# Matrix.net
KiCad netlist of a schematic drawn in Altium Designer
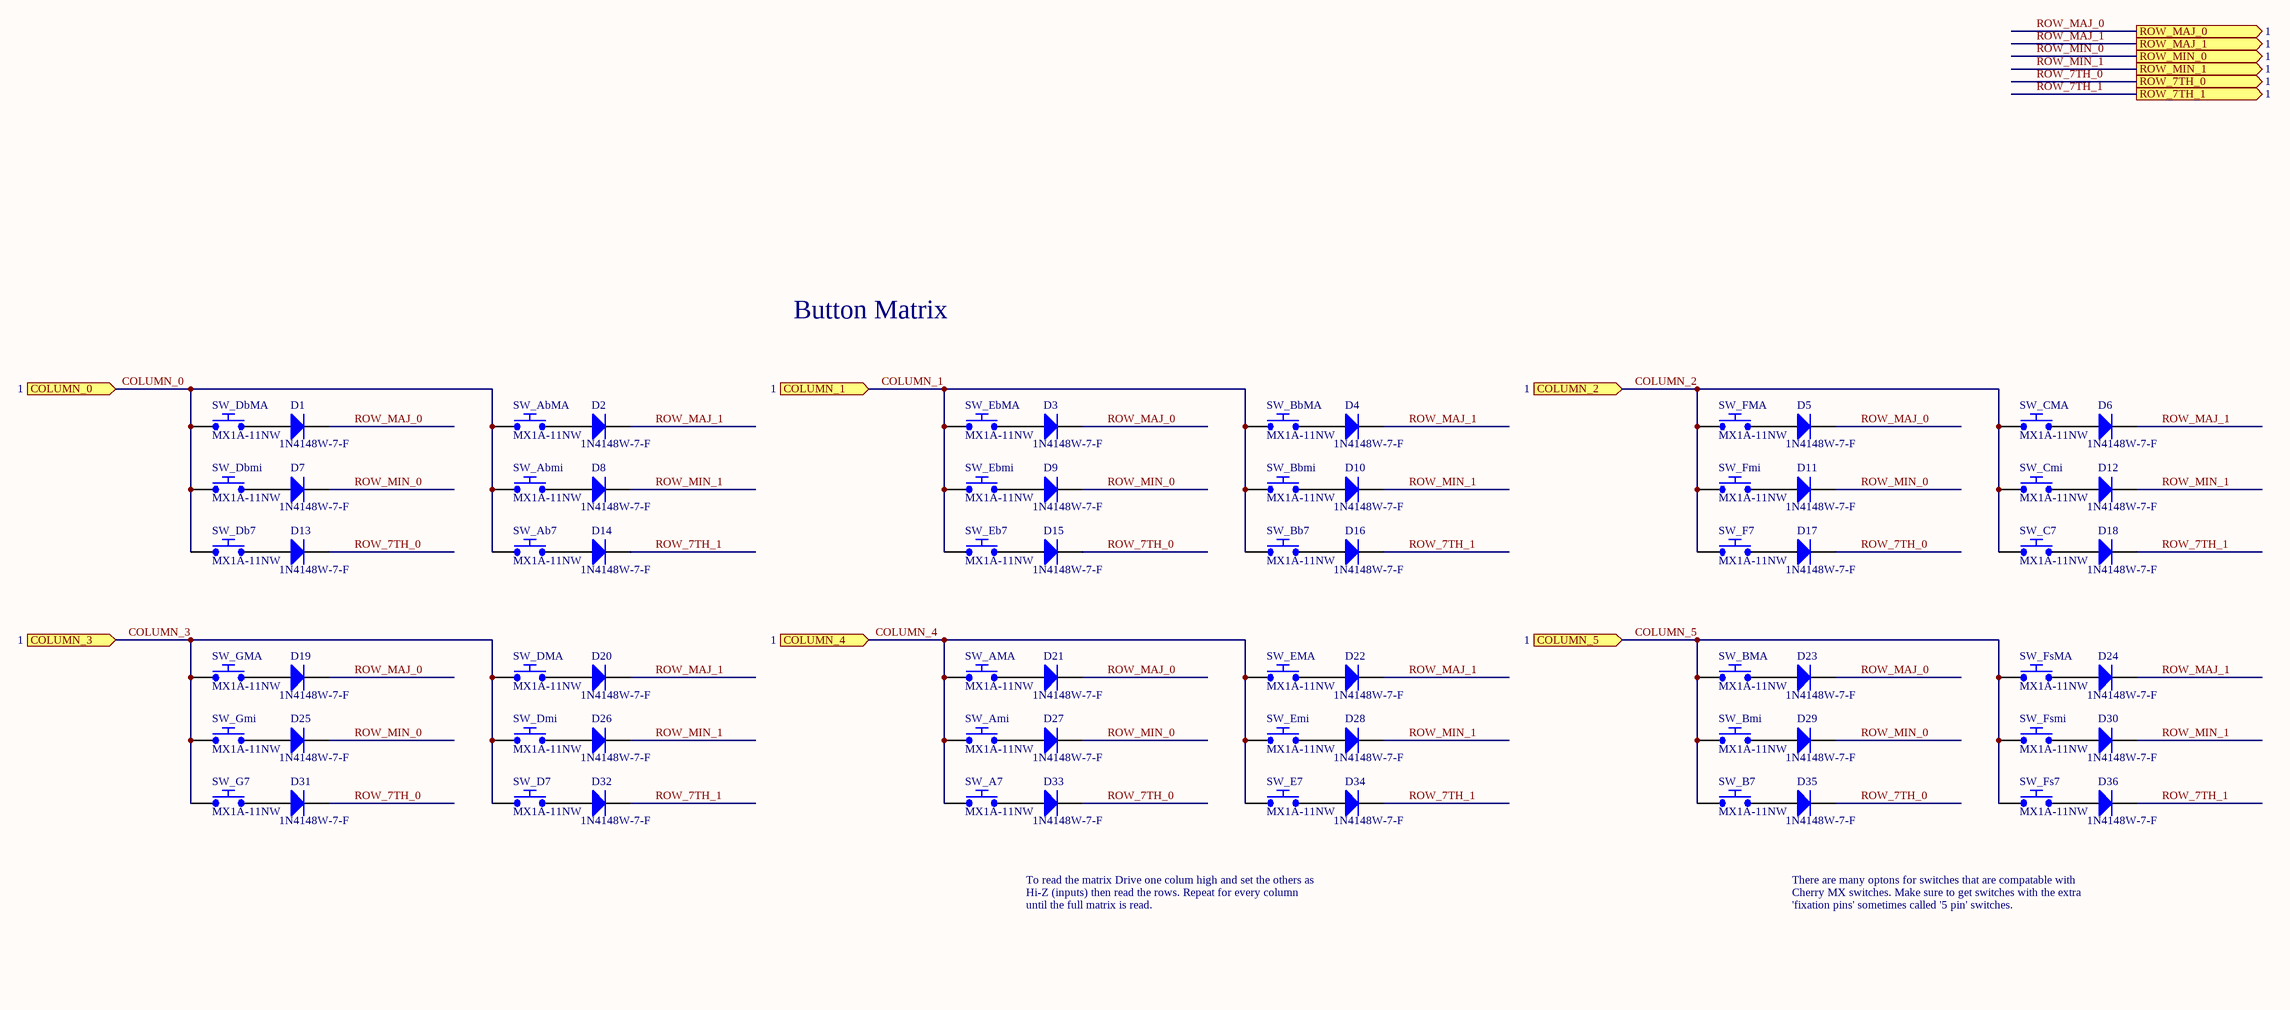
[diagram p0: Matrix.SchDoc]

(export (version "E")
  (design (tool "Eeschema 10.0.6"))
  (components
    (comp (ref "D1")
      (value "1N4148W-7-F")
      (footprint "SOD-123")
      (description "DIODE SWITCH 100V 0.15A SOD123")
      (fields (field (name "MANUFACTURER") "Diodes Incorporated"))
      (libsource (lib "Semiconductor") (part "DIODE"))
    )
    (comp (ref "D2")
      (value "1N4148W-7-F")
      (footprint "SOD-123")
      (description "DIODE SWITCH 100V 0.15A SOD123")
      (fields (field (name "MANUFACTURER") "Diodes Incorporated"))
      (libsource (lib "Semiconductor") (part "DIODE"))
    )
    (comp (ref "D3")
      (value "1N4148W-7-F")
      (footprint "SOD-123")
      (description "DIODE SWITCH 100V 0.15A SOD123")
      (fields (field (name "MANUFACTURER") "Diodes Incorporated"))
      (libsource (lib "Semiconductor") (part "DIODE"))
    )
    (comp (ref "D4")
      (value "1N4148W-7-F")
      (footprint "SOD-123")
      (description "DIODE SWITCH 100V 0.15A SOD123")
      (fields (field (name "MANUFACTURER") "Diodes Incorporated"))
      (libsource (lib "Semiconductor") (part "DIODE"))
    )
    (comp (ref "D5")
      (value "1N4148W-7-F")
      (footprint "SOD-123")
      (description "DIODE SWITCH 100V 0.15A SOD123")
      (fields (field (name "MANUFACTURER") "Diodes Incorporated"))
      (libsource (lib "Semiconductor") (part "DIODE"))
    )
    (comp (ref "D6")
      (value "1N4148W-7-F")
      (footprint "SOD-123")
      (description "DIODE SWITCH 100V 0.15A SOD123")
      (fields (field (name "MANUFACTURER") "Diodes Incorporated"))
      (libsource (lib "Semiconductor") (part "DIODE"))
    )
    (comp (ref "D7")
      (value "1N4148W-7-F")
      (footprint "SOD-123")
      (description "DIODE SWITCH 100V 0.15A SOD123")
      (fields (field (name "MANUFACTURER") "Diodes Incorporated"))
      (libsource (lib "Semiconductor") (part "DIODE"))
    )
    (comp (ref "D8")
      (value "1N4148W-7-F")
      (footprint "SOD-123")
      (description "DIODE SWITCH 100V 0.15A SOD123")
      (fields (field (name "MANUFACTURER") "Diodes Incorporated"))
      (libsource (lib "Semiconductor") (part "DIODE"))
    )
    (comp (ref "D9")
      (value "1N4148W-7-F")
      (footprint "SOD-123")
      (description "DIODE SWITCH 100V 0.15A SOD123")
      (fields (field (name "MANUFACTURER") "Diodes Incorporated"))
      (libsource (lib "Semiconductor") (part "DIODE"))
    )
    (comp (ref "D10")
      (value "1N4148W-7-F")
      (footprint "SOD-123")
      (description "DIODE SWITCH 100V 0.15A SOD123")
      (fields (field (name "MANUFACTURER") "Diodes Incorporated"))
      (libsource (lib "Semiconductor") (part "DIODE"))
    )
    (comp (ref "D11")
      (value "1N4148W-7-F")
      (footprint "SOD-123")
      (description "DIODE SWITCH 100V 0.15A SOD123")
      (fields (field (name "MANUFACTURER") "Diodes Incorporated"))
      (libsource (lib "Semiconductor") (part "DIODE"))
    )
    (comp (ref "D12")
      (value "1N4148W-7-F")
      (footprint "SOD-123")
      (description "DIODE SWITCH 100V 0.15A SOD123")
      (fields (field (name "MANUFACTURER") "Diodes Incorporated"))
      (libsource (lib "Semiconductor") (part "DIODE"))
    )
    (comp (ref "D13")
      (value "1N4148W-7-F")
      (footprint "SOD-123")
      (description "DIODE SWITCH 100V 0.15A SOD123")
      (fields (field (name "MANUFACTURER") "Diodes Incorporated"))
      (libsource (lib "Semiconductor") (part "DIODE"))
    )
    (comp (ref "D14")
      (value "1N4148W-7-F")
      (footprint "SOD-123")
      (description "DIODE SWITCH 100V 0.15A SOD123")
      (fields (field (name "MANUFACTURER") "Diodes Incorporated"))
      (libsource (lib "Semiconductor") (part "DIODE"))
    )
    (comp (ref "D15")
      (value "1N4148W-7-F")
      (footprint "SOD-123")
      (description "DIODE SWITCH 100V 0.15A SOD123")
      (fields (field (name "MANUFACTURER") "Diodes Incorporated"))
      (libsource (lib "Semiconductor") (part "DIODE"))
    )
    (comp (ref "D16")
      (value "1N4148W-7-F")
      (footprint "SOD-123")
      (description "DIODE SWITCH 100V 0.15A SOD123")
      (fields (field (name "MANUFACTURER") "Diodes Incorporated"))
      (libsource (lib "Semiconductor") (part "DIODE"))
    )
    (comp (ref "D17")
      (value "1N4148W-7-F")
      (footprint "SOD-123")
      (description "DIODE SWITCH 100V 0.15A SOD123")
      (fields (field (name "MANUFACTURER") "Diodes Incorporated"))
      (libsource (lib "Semiconductor") (part "DIODE"))
    )
    (comp (ref "D18")
      (value "1N4148W-7-F")
      (footprint "SOD-123")
      (description "DIODE SWITCH 100V 0.15A SOD123")
      (fields (field (name "MANUFACTURER") "Diodes Incorporated"))
      (libsource (lib "Semiconductor") (part "DIODE"))
    )
    (comp (ref "D19")
      (value "1N4148W-7-F")
      (footprint "SOD-123")
      (description "DIODE SWITCH 100V 0.15A SOD123")
      (fields (field (name "MANUFACTURER") "Diodes Incorporated"))
      (libsource (lib "Semiconductor") (part "DIODE"))
    )
    (comp (ref "D20")
      (value "1N4148W-7-F")
      (footprint "SOD-123")
      (description "DIODE SWITCH 100V 0.15A SOD123")
      (fields (field (name "MANUFACTURER") "Diodes Incorporated"))
      (libsource (lib "Semiconductor") (part "DIODE"))
    )
    (comp (ref "D21")
      (value "1N4148W-7-F")
      (footprint "SOD-123")
      (description "DIODE SWITCH 100V 0.15A SOD123")
      (fields (field (name "MANUFACTURER") "Diodes Incorporated"))
      (libsource (lib "Semiconductor") (part "DIODE"))
    )
    (comp (ref "D22")
      (value "1N4148W-7-F")
      (footprint "SOD-123")
      (description "DIODE SWITCH 100V 0.15A SOD123")
      (fields (field (name "MANUFACTURER") "Diodes Incorporated"))
      (libsource (lib "Semiconductor") (part "DIODE"))
    )
    (comp (ref "D23")
      (value "1N4148W-7-F")
      (footprint "SOD-123")
      (description "DIODE SWITCH 100V 0.15A SOD123")
      (fields (field (name "MANUFACTURER") "Diodes Incorporated"))
      (libsource (lib "Semiconductor") (part "DIODE"))
    )
    (comp (ref "D24")
      (value "1N4148W-7-F")
      (footprint "SOD-123")
      (description "DIODE SWITCH 100V 0.15A SOD123")
      (fields (field (name "MANUFACTURER") "Diodes Incorporated"))
      (libsource (lib "Semiconductor") (part "DIODE"))
    )
    (comp (ref "D25")
      (value "1N4148W-7-F")
      (footprint "SOD-123")
      (description "DIODE SWITCH 100V 0.15A SOD123")
      (fields (field (name "MANUFACTURER") "Diodes Incorporated"))
      (libsource (lib "Semiconductor") (part "DIODE"))
    )
    (comp (ref "D26")
      (value "1N4148W-7-F")
      (footprint "SOD-123")
      (description "DIODE SWITCH 100V 0.15A SOD123")
      (fields (field (name "MANUFACTURER") "Diodes Incorporated"))
      (libsource (lib "Semiconductor") (part "DIODE"))
    )
    (comp (ref "D27")
      (value "1N4148W-7-F")
      (footprint "SOD-123")
      (description "DIODE SWITCH 100V 0.15A SOD123")
      (fields (field (name "MANUFACTURER") "Diodes Incorporated"))
      (libsource (lib "Semiconductor") (part "DIODE"))
    )
    (comp (ref "D28")
      (value "1N4148W-7-F")
      (footprint "SOD-123")
      (description "DIODE SWITCH 100V 0.15A SOD123")
      (fields (field (name "MANUFACTURER") "Diodes Incorporated"))
      (libsource (lib "Semiconductor") (part "DIODE"))
    )
    (comp (ref "D29")
      (value "1N4148W-7-F")
      (footprint "SOD-123")
      (description "DIODE SWITCH 100V 0.15A SOD123")
      (fields (field (name "MANUFACTURER") "Diodes Incorporated"))
      (libsource (lib "Semiconductor") (part "DIODE"))
    )
    (comp (ref "D30")
      (value "1N4148W-7-F")
      (footprint "SOD-123")
      (description "DIODE SWITCH 100V 0.15A SOD123")
      (fields (field (name "MANUFACTURER") "Diodes Incorporated"))
      (libsource (lib "Semiconductor") (part "DIODE"))
    )
    (comp (ref "D31")
      (value "1N4148W-7-F")
      (footprint "SOD-123")
      (description "DIODE SWITCH 100V 0.15A SOD123")
      (fields (field (name "MANUFACTURER") "Diodes Incorporated"))
      (libsource (lib "Semiconductor") (part "DIODE"))
    )
    (comp (ref "D32")
      (value "1N4148W-7-F")
      (footprint "SOD-123")
      (description "DIODE SWITCH 100V 0.15A SOD123")
      (fields (field (name "MANUFACTURER") "Diodes Incorporated"))
      (libsource (lib "Semiconductor") (part "DIODE"))
    )
    (comp (ref "D33")
      (value "1N4148W-7-F")
      (footprint "SOD-123")
      (description "DIODE SWITCH 100V 0.15A SOD123")
      (fields (field (name "MANUFACTURER") "Diodes Incorporated"))
      (libsource (lib "Semiconductor") (part "DIODE"))
    )
    (comp (ref "D34")
      (value "1N4148W-7-F")
      (footprint "SOD-123")
      (description "DIODE SWITCH 100V 0.15A SOD123")
      (fields (field (name "MANUFACTURER") "Diodes Incorporated"))
      (libsource (lib "Semiconductor") (part "DIODE"))
    )
    (comp (ref "D35")
      (value "1N4148W-7-F")
      (footprint "SOD-123")
      (description "DIODE SWITCH 100V 0.15A SOD123")
      (fields (field (name "MANUFACTURER") "Diodes Incorporated"))
      (libsource (lib "Semiconductor") (part "DIODE"))
    )
    (comp (ref "D36")
      (value "1N4148W-7-F")
      (footprint "SOD-123")
      (description "DIODE SWITCH 100V 0.15A SOD123")
      (fields (field (name "MANUFACTURER") "Diodes Incorporated"))
      (libsource (lib "Semiconductor") (part "DIODE"))
    )
    (comp (ref "SW_A7")
      (value "MX1A-11NW")
      (footprint "CHERRY_MX_FIX")
      (description "SWITCH PUSH SPST-NO 0.01A 12V")
      (fields (field (name "MANUFACTURER") "Cherry Americas LLC"))
      (libsource (lib "Switches") (part "SWITCH_SPST_PUSH_NO"))
    )
    (comp (ref "SW_Ab7")
      (value "MX1A-11NW")
      (footprint "CHERRY_MX_FIX")
      (description "SWITCH PUSH SPST-NO 0.01A 12V")
      (fields (field (name "MANUFACTURER") "Cherry Americas LLC"))
      (libsource (lib "Switches") (part "SWITCH_SPST_PUSH_NO"))
    )
    (comp (ref "SW_AbMA")
      (value "MX1A-11NW")
      (footprint "CHERRY_MX_FIX")
      (description "SWITCH PUSH SPST-NO 0.01A 12V")
      (fields (field (name "MANUFACTURER") "Cherry Americas LLC"))
      (libsource (lib "Switches") (part "SWITCH_SPST_PUSH_NO"))
    )
    (comp (ref "SW_Abmi")
      (value "MX1A-11NW")
      (footprint "CHERRY_MX_FIX")
      (description "SWITCH PUSH SPST-NO 0.01A 12V")
      (fields (field (name "MANUFACTURER") "Cherry Americas LLC"))
      (libsource (lib "Switches") (part "SWITCH_SPST_PUSH_NO"))
    )
    (comp (ref "SW_AMA")
      (value "MX1A-11NW")
      (footprint "CHERRY_MX_FIX")
      (description "SWITCH PUSH SPST-NO 0.01A 12V")
      (fields (field (name "MANUFACTURER") "Cherry Americas LLC"))
      (libsource (lib "Switches") (part "SWITCH_SPST_PUSH_NO"))
    )
    (comp (ref "SW_Ami")
      (value "MX1A-11NW")
      (footprint "CHERRY_MX_FIX")
      (description "SWITCH PUSH SPST-NO 0.01A 12V")
      (fields (field (name "MANUFACTURER") "Cherry Americas LLC"))
      (libsource (lib "Switches") (part "SWITCH_SPST_PUSH_NO"))
    )
    (comp (ref "SW_B7")
      (value "MX1A-11NW")
      (footprint "CHERRY_MX_FIX")
      (description "SWITCH PUSH SPST-NO 0.01A 12V")
      (fields (field (name "MANUFACTURER") "Cherry Americas LLC"))
      (libsource (lib "Switches") (part "SWITCH_SPST_PUSH_NO"))
    )
    (comp (ref "SW_Bb7")
      (value "MX1A-11NW")
      (footprint "CHERRY_MX_FIX")
      (description "SWITCH PUSH SPST-NO 0.01A 12V")
      (fields (field (name "MANUFACTURER") "Cherry Americas LLC"))
      (libsource (lib "Switches") (part "SWITCH_SPST_PUSH_NO"))
    )
    (comp (ref "SW_BbMA")
      (value "MX1A-11NW")
      (footprint "CHERRY_MX_FIX")
      (description "SWITCH PUSH SPST-NO 0.01A 12V")
      (fields (field (name "MANUFACTURER") "Cherry Americas LLC"))
      (libsource (lib "Switches") (part "SWITCH_SPST_PUSH_NO"))
    )
    (comp (ref "SW_Bbmi")
      (value "MX1A-11NW")
      (footprint "CHERRY_MX_FIX")
      (description "SWITCH PUSH SPST-NO 0.01A 12V")
      (fields (field (name "MANUFACTURER") "Cherry Americas LLC"))
      (libsource (lib "Switches") (part "SWITCH_SPST_PUSH_NO"))
    )
    (comp (ref "SW_BMA")
      (value "MX1A-11NW")
      (footprint "CHERRY_MX_FIX")
      (description "SWITCH PUSH SPST-NO 0.01A 12V")
      (fields (field (name "MANUFACTURER") "Cherry Americas LLC"))
      (libsource (lib "Switches") (part "SWITCH_SPST_PUSH_NO"))
    )
    (comp (ref "SW_Bmi")
      (value "MX1A-11NW")
      (footprint "CHERRY_MX_FIX")
      (description "SWITCH PUSH SPST-NO 0.01A 12V")
      (fields (field (name "MANUFACTURER") "Cherry Americas LLC"))
      (libsource (lib "Switches") (part "SWITCH_SPST_PUSH_NO"))
    )
    (comp (ref "SW_C7")
      (value "MX1A-11NW")
      (footprint "CHERRY_MX_FIX")
      (description "SWITCH PUSH SPST-NO 0.01A 12V")
      (fields (field (name "MANUFACTURER") "Cherry Americas LLC"))
      (libsource (lib "Switches") (part "SWITCH_SPST_PUSH_NO"))
    )
    (comp (ref "SW_CMA")
      (value "MX1A-11NW")
      (footprint "CHERRY_MX_FIX")
      (description "SWITCH PUSH SPST-NO 0.01A 12V")
      (fields (field (name "MANUFACTURER") "Cherry Americas LLC"))
      (libsource (lib "Switches") (part "SWITCH_SPST_PUSH_NO"))
    )
    (comp (ref "SW_Cmi")
      (value "MX1A-11NW")
      (footprint "CHERRY_MX_FIX")
      (description "SWITCH PUSH SPST-NO 0.01A 12V")
      (fields (field (name "MANUFACTURER") "Cherry Americas LLC"))
      (libsource (lib "Switches") (part "SWITCH_SPST_PUSH_NO"))
    )
    (comp (ref "SW_D7")
      (value "MX1A-11NW")
      (footprint "CHERRY_MX_FIX")
      (description "SWITCH PUSH SPST-NO 0.01A 12V")
      (fields (field (name "MANUFACTURER") "Cherry Americas LLC"))
      (libsource (lib "Switches") (part "SWITCH_SPST_PUSH_NO"))
    )
    (comp (ref "SW_Db7")
      (value "MX1A-11NW")
      (footprint "CHERRY_MX_FIX")
      (description "SWITCH PUSH SPST-NO 0.01A 12V")
      (fields (field (name "MANUFACTURER") "Cherry Americas LLC"))
      (libsource (lib "Switches") (part "SWITCH_SPST_PUSH_NO"))
    )
    (comp (ref "SW_DbMA")
      (value "MX1A-11NW")
      (footprint "CHERRY_MX_FIX")
      (description "SWITCH PUSH SPST-NO 0.01A 12V")
      (fields (field (name "MANUFACTURER") "Cherry Americas LLC"))
      (libsource (lib "Switches") (part "SWITCH_SPST_PUSH_NO"))
    )
    (comp (ref "SW_Dbmi")
      (value "MX1A-11NW")
      (footprint "CHERRY_MX_FIX")
      (description "SWITCH PUSH SPST-NO 0.01A 12V")
      (fields (field (name "MANUFACTURER") "Cherry Americas LLC"))
      (libsource (lib "Switches") (part "SWITCH_SPST_PUSH_NO"))
    )
    (comp (ref "SW_DMA")
      (value "MX1A-11NW")
      (footprint "CHERRY_MX_FIX")
      (description "SWITCH PUSH SPST-NO 0.01A 12V")
      (fields (field (name "MANUFACTURER") "Cherry Americas LLC"))
      (libsource (lib "Switches") (part "SWITCH_SPST_PUSH_NO"))
    )
    (comp (ref "SW_Dmi")
      (value "MX1A-11NW")
      (footprint "CHERRY_MX_FIX")
      (description "SWITCH PUSH SPST-NO 0.01A 12V")
      (fields (field (name "MANUFACTURER") "Cherry Americas LLC"))
      (libsource (lib "Switches") (part "SWITCH_SPST_PUSH_NO"))
    )
    (comp (ref "SW_E7")
      (value "MX1A-11NW")
      (footprint "CHERRY_MX_FIX")
      (description "SWITCH PUSH SPST-NO 0.01A 12V")
      (fields (field (name "MANUFACTURER") "Cherry Americas LLC"))
      (libsource (lib "Switches") (part "SWITCH_SPST_PUSH_NO"))
    )
    (comp (ref "SW_Eb7")
      (value "MX1A-11NW")
      (footprint "CHERRY_MX_FIX")
      (description "SWITCH PUSH SPST-NO 0.01A 12V")
      (fields (field (name "MANUFACTURER") "Cherry Americas LLC"))
      (libsource (lib "Switches") (part "SWITCH_SPST_PUSH_NO"))
    )
    (comp (ref "SW_EbMA")
      (value "MX1A-11NW")
      (footprint "CHERRY_MX_FIX")
      (description "SWITCH PUSH SPST-NO 0.01A 12V")
      (fields (field (name "MANUFACTURER") "Cherry Americas LLC"))
      (libsource (lib "Switches") (part "SWITCH_SPST_PUSH_NO"))
    )
    (comp (ref "SW_Ebmi")
      (value "MX1A-11NW")
      (footprint "CHERRY_MX_FIX")
      (description "SWITCH PUSH SPST-NO 0.01A 12V")
      (fields (field (name "MANUFACTURER") "Cherry Americas LLC"))
      (libsource (lib "Switches") (part "SWITCH_SPST_PUSH_NO"))
    )
    (comp (ref "SW_EMA")
      (value "MX1A-11NW")
      (footprint "CHERRY_MX_FIX")
      (description "SWITCH PUSH SPST-NO 0.01A 12V")
      (fields (field (name "MANUFACTURER") "Cherry Americas LLC"))
      (libsource (lib "Switches") (part "SWITCH_SPST_PUSH_NO"))
    )
    (comp (ref "SW_Emi")
      (value "MX1A-11NW")
      (footprint "CHERRY_MX_FIX")
      (description "SWITCH PUSH SPST-NO 0.01A 12V")
      (fields (field (name "MANUFACTURER") "Cherry Americas LLC"))
      (libsource (lib "Switches") (part "SWITCH_SPST_PUSH_NO"))
    )
    (comp (ref "SW_F7")
      (value "MX1A-11NW")
      (footprint "CHERRY_MX_FIX")
      (description "SWITCH PUSH SPST-NO 0.01A 12V")
      (fields (field (name "MANUFACTURER") "Cherry Americas LLC"))
      (libsource (lib "Switches") (part "SWITCH_SPST_PUSH_NO"))
    )
    (comp (ref "SW_FMA")
      (value "MX1A-11NW")
      (footprint "CHERRY_MX_FIX")
      (description "SWITCH PUSH SPST-NO 0.01A 12V")
      (fields (field (name "MANUFACTURER") "Cherry Americas LLC"))
      (libsource (lib "Switches") (part "SWITCH_SPST_PUSH_NO"))
    )
    (comp (ref "SW_Fmi")
      (value "MX1A-11NW")
      (footprint "CHERRY_MX_FIX")
      (description "SWITCH PUSH SPST-NO 0.01A 12V")
      (fields (field (name "MANUFACTURER") "Cherry Americas LLC"))
      (libsource (lib "Switches") (part "SWITCH_SPST_PUSH_NO"))
    )
    (comp (ref "SW_Fs7")
      (value "MX1A-11NW")
      (footprint "CHERRY_MX_FIX")
      (description "SWITCH PUSH SPST-NO 0.01A 12V")
      (fields (field (name "MANUFACTURER") "Cherry Americas LLC"))
      (libsource (lib "Switches") (part "SWITCH_SPST_PUSH_NO"))
    )
    (comp (ref "SW_FsMA")
      (value "MX1A-11NW")
      (footprint "CHERRY_MX_FIX")
      (description "SWITCH PUSH SPST-NO 0.01A 12V")
      (fields (field (name "MANUFACTURER") "Cherry Americas LLC"))
      (libsource (lib "Switches") (part "SWITCH_SPST_PUSH_NO"))
    )
    (comp (ref "SW_Fsmi")
      (value "MX1A-11NW")
      (footprint "CHERRY_MX_FIX")
      (description "SWITCH PUSH SPST-NO 0.01A 12V")
      (fields (field (name "MANUFACTURER") "Cherry Americas LLC"))
      (libsource (lib "Switches") (part "SWITCH_SPST_PUSH_NO"))
    )
    (comp (ref "SW_G7")
      (value "MX1A-11NW")
      (footprint "CHERRY_MX_FIX")
      (description "SWITCH PUSH SPST-NO 0.01A 12V")
      (fields (field (name "MANUFACTURER") "Cherry Americas LLC"))
      (libsource (lib "Switches") (part "SWITCH_SPST_PUSH_NO"))
    )
    (comp (ref "SW_GMA")
      (value "MX1A-11NW")
      (footprint "CHERRY_MX_FIX")
      (description "SWITCH PUSH SPST-NO 0.01A 12V")
      (fields (field (name "MANUFACTURER") "Cherry Americas LLC"))
      (libsource (lib "Switches") (part "SWITCH_SPST_PUSH_NO"))
    )
    (comp (ref "SW_Gmi")
      (value "MX1A-11NW")
      (footprint "CHERRY_MX_FIX")
      (description "SWITCH PUSH SPST-NO 0.01A 12V")
      (fields (field (name "MANUFACTURER") "Cherry Americas LLC"))
      (libsource (lib "Switches") (part "SWITCH_SPST_PUSH_NO"))
    )
  )
  (nets
    (net (code "1") (name "/COLUMN_0") (class "Default")
      (node (ref "SW_Ab7") (pin "1") (pinfunction "1_1") (pintype "passive"))
      (node (ref "SW_AbMA") (pin "1") (pinfunction "1_1") (pintype "passive"))
      (node (ref "SW_Abmi") (pin "1") (pinfunction "1_1") (pintype "passive"))
      (node (ref "SW_Db7") (pin "1") (pinfunction "1_1") (pintype "passive"))
      (node (ref "SW_DbMA") (pin "1") (pinfunction "1_1") (pintype "passive"))
      (node (ref "SW_Dbmi") (pin "1") (pinfunction "1_1") (pintype "passive"))
    )
    (net (code "2") (name "/COLUMN_1") (class "Default")
      (node (ref "SW_Bb7") (pin "1") (pinfunction "1_1") (pintype "passive"))
      (node (ref "SW_BbMA") (pin "1") (pinfunction "1_1") (pintype "passive"))
      (node (ref "SW_Bbmi") (pin "1") (pinfunction "1_1") (pintype "passive"))
      (node (ref "SW_Eb7") (pin "1") (pinfunction "1_1") (pintype "passive"))
      (node (ref "SW_EbMA") (pin "1") (pinfunction "1_1") (pintype "passive"))
      (node (ref "SW_Ebmi") (pin "1") (pinfunction "1_1") (pintype "passive"))
    )
    (net (code "3") (name "/COLUMN_2") (class "Default")
      (node (ref "SW_C7") (pin "1") (pinfunction "1_1") (pintype "passive"))
      (node (ref "SW_CMA") (pin "1") (pinfunction "1_1") (pintype "passive"))
      (node (ref "SW_Cmi") (pin "1") (pinfunction "1_1") (pintype "passive"))
      (node (ref "SW_F7") (pin "1") (pinfunction "1_1") (pintype "passive"))
      (node (ref "SW_FMA") (pin "1") (pinfunction "1_1") (pintype "passive"))
      (node (ref "SW_Fmi") (pin "1") (pinfunction "1_1") (pintype "passive"))
    )
    (net (code "4") (name "/COLUMN_3") (class "Default")
      (node (ref "SW_D7") (pin "1") (pinfunction "1_1") (pintype "passive"))
      (node (ref "SW_DMA") (pin "1") (pinfunction "1_1") (pintype "passive"))
      (node (ref "SW_Dmi") (pin "1") (pinfunction "1_1") (pintype "passive"))
      (node (ref "SW_G7") (pin "1") (pinfunction "1_1") (pintype "passive"))
      (node (ref "SW_GMA") (pin "1") (pinfunction "1_1") (pintype "passive"))
      (node (ref "SW_Gmi") (pin "1") (pinfunction "1_1") (pintype "passive"))
    )
    (net (code "5") (name "/COLUMN_4") (class "Default")
      (node (ref "SW_A7") (pin "1") (pinfunction "1_1") (pintype "passive"))
      (node (ref "SW_AMA") (pin "1") (pinfunction "1_1") (pintype "passive"))
      (node (ref "SW_Ami") (pin "1") (pinfunction "1_1") (pintype "passive"))
      (node (ref "SW_E7") (pin "1") (pinfunction "1_1") (pintype "passive"))
      (node (ref "SW_EMA") (pin "1") (pinfunction "1_1") (pintype "passive"))
      (node (ref "SW_Emi") (pin "1") (pinfunction "1_1") (pintype "passive"))
    )
    (net (code "6") (name "/COLUMN_5") (class "Default")
      (node (ref "SW_B7") (pin "1") (pinfunction "1_1") (pintype "passive"))
      (node (ref "SW_BMA") (pin "1") (pinfunction "1_1") (pintype "passive"))
      (node (ref "SW_Bmi") (pin "1") (pinfunction "1_1") (pintype "passive"))
      (node (ref "SW_Fs7") (pin "1") (pinfunction "1_1") (pintype "passive"))
      (node (ref "SW_FsMA") (pin "1") (pinfunction "1_1") (pintype "passive"))
      (node (ref "SW_Fsmi") (pin "1") (pinfunction "1_1") (pintype "passive"))
    )
    (net (code "7") (name "/ROW_7TH_0") (class "Default")
      (node (ref "D13") (pin "1") (pinfunction "C_1") (pintype "passive"))
      (node (ref "D15") (pin "1") (pinfunction "C_1") (pintype "passive"))
      (node (ref "D17") (pin "1") (pinfunction "C_1") (pintype "passive"))
      (node (ref "D31") (pin "1") (pinfunction "C_1") (pintype "passive"))
      (node (ref "D33") (pin "1") (pinfunction "C_1") (pintype "passive"))
      (node (ref "D35") (pin "1") (pinfunction "C_1") (pintype "passive"))
    )
    (net (code "8") (name "/ROW_7TH_1") (class "Default")
      (node (ref "D14") (pin "1") (pinfunction "C_1") (pintype "passive"))
      (node (ref "D16") (pin "1") (pinfunction "C_1") (pintype "passive"))
      (node (ref "D18") (pin "1") (pinfunction "C_1") (pintype "passive"))
      (node (ref "D32") (pin "1") (pinfunction "C_1") (pintype "passive"))
      (node (ref "D34") (pin "1") (pinfunction "C_1") (pintype "passive"))
      (node (ref "D36") (pin "1") (pinfunction "C_1") (pintype "passive"))
    )
    (net (code "9") (name "/ROW_MAJ_0") (class "Default")
      (node (ref "D1") (pin "1") (pinfunction "C_1") (pintype "passive"))
      (node (ref "D19") (pin "1") (pinfunction "C_1") (pintype "passive"))
      (node (ref "D21") (pin "1") (pinfunction "C_1") (pintype "passive"))
      (node (ref "D23") (pin "1") (pinfunction "C_1") (pintype "passive"))
      (node (ref "D3") (pin "1") (pinfunction "C_1") (pintype "passive"))
      (node (ref "D5") (pin "1") (pinfunction "C_1") (pintype "passive"))
    )
    (net (code "10") (name "/ROW_MAJ_1") (class "Default")
      (node (ref "D2") (pin "1") (pinfunction "C_1") (pintype "passive"))
      (node (ref "D20") (pin "1") (pinfunction "C_1") (pintype "passive"))
      (node (ref "D22") (pin "1") (pinfunction "C_1") (pintype "passive"))
      (node (ref "D24") (pin "1") (pinfunction "C_1") (pintype "passive"))
      (node (ref "D4") (pin "1") (pinfunction "C_1") (pintype "passive"))
      (node (ref "D6") (pin "1") (pinfunction "C_1") (pintype "passive"))
    )
    (net (code "11") (name "/ROW_MIN_0") (class "Default")
      (node (ref "D11") (pin "1") (pinfunction "C_1") (pintype "passive"))
      (node (ref "D25") (pin "1") (pinfunction "C_1") (pintype "passive"))
      (node (ref "D27") (pin "1") (pinfunction "C_1") (pintype "passive"))
      (node (ref "D29") (pin "1") (pinfunction "C_1") (pintype "passive"))
      (node (ref "D7") (pin "1") (pinfunction "C_1") (pintype "passive"))
      (node (ref "D9") (pin "1") (pinfunction "C_1") (pintype "passive"))
    )
    (net (code "12") (name "/ROW_MIN_1") (class "Default")
      (node (ref "D10") (pin "1") (pinfunction "C_1") (pintype "passive"))
      (node (ref "D12") (pin "1") (pinfunction "C_1") (pintype "passive"))
      (node (ref "D26") (pin "1") (pinfunction "C_1") (pintype "passive"))
      (node (ref "D28") (pin "1") (pinfunction "C_1") (pintype "passive"))
      (node (ref "D30") (pin "1") (pinfunction "C_1") (pintype "passive"))
      (node (ref "D8") (pin "1") (pinfunction "C_1") (pintype "passive"))
    )
    (net (code "13") (name "Net-(D1-A)") (class "Default")
      (node (ref "D1") (pin "2") (pinfunction "A_2") (pintype "passive"))
      (node (ref "SW_DbMA") (pin "2") (pinfunction "2_2") (pintype "passive"))
    )
    (net (code "14") (name "Net-(D2-A)") (class "Default")
      (node (ref "D2") (pin "2") (pinfunction "A_2") (pintype "passive"))
      (node (ref "SW_AbMA") (pin "2") (pinfunction "2_2") (pintype "passive"))
    )
    (net (code "15") (name "Net-(D3-A)") (class "Default")
      (node (ref "D3") (pin "2") (pinfunction "A_2") (pintype "passive"))
      (node (ref "SW_EbMA") (pin "2") (pinfunction "2_2") (pintype "passive"))
    )
    (net (code "16") (name "Net-(D4-A)") (class "Default")
      (node (ref "D4") (pin "2") (pinfunction "A_2") (pintype "passive"))
      (node (ref "SW_BbMA") (pin "2") (pinfunction "2_2") (pintype "passive"))
    )
    (net (code "17") (name "Net-(D5-A)") (class "Default")
      (node (ref "D5") (pin "2") (pinfunction "A_2") (pintype "passive"))
      (node (ref "SW_FMA") (pin "2") (pinfunction "2_2") (pintype "passive"))
    )
    (net (code "18") (name "Net-(D6-A)") (class "Default")
      (node (ref "D6") (pin "2") (pinfunction "A_2") (pintype "passive"))
      (node (ref "SW_CMA") (pin "2") (pinfunction "2_2") (pintype "passive"))
    )
    (net (code "19") (name "Net-(D7-A)") (class "Default")
      (node (ref "D7") (pin "2") (pinfunction "A_2") (pintype "passive"))
      (node (ref "SW_Dbmi") (pin "2") (pinfunction "2_2") (pintype "passive"))
    )
    (net (code "20") (name "Net-(D8-A)") (class "Default")
      (node (ref "D8") (pin "2") (pinfunction "A_2") (pintype "passive"))
      (node (ref "SW_Abmi") (pin "2") (pinfunction "2_2") (pintype "passive"))
    )
    (net (code "21") (name "Net-(D9-A)") (class "Default")
      (node (ref "D9") (pin "2") (pinfunction "A_2") (pintype "passive"))
      (node (ref "SW_Ebmi") (pin "2") (pinfunction "2_2") (pintype "passive"))
    )
    (net (code "22") (name "Net-(D10-A)") (class "Default")
      (node (ref "D10") (pin "2") (pinfunction "A_2") (pintype "passive"))
      (node (ref "SW_Bbmi") (pin "2") (pinfunction "2_2") (pintype "passive"))
    )
    (net (code "23") (name "Net-(D11-A)") (class "Default")
      (node (ref "D11") (pin "2") (pinfunction "A_2") (pintype "passive"))
      (node (ref "SW_Fmi") (pin "2") (pinfunction "2_2") (pintype "passive"))
    )
    (net (code "24") (name "Net-(D12-A)") (class "Default")
      (node (ref "D12") (pin "2") (pinfunction "A_2") (pintype "passive"))
      (node (ref "SW_Cmi") (pin "2") (pinfunction "2_2") (pintype "passive"))
    )
    (net (code "25") (name "Net-(D13-A)") (class "Default")
      (node (ref "D13") (pin "2") (pinfunction "A_2") (pintype "passive"))
      (node (ref "SW_Db7") (pin "2") (pinfunction "2_2") (pintype "passive"))
    )
    (net (code "26") (name "Net-(D14-A)") (class "Default")
      (node (ref "D14") (pin "2") (pinfunction "A_2") (pintype "passive"))
      (node (ref "SW_Ab7") (pin "2") (pinfunction "2_2") (pintype "passive"))
    )
    (net (code "27") (name "Net-(D15-A)") (class "Default")
      (node (ref "D15") (pin "2") (pinfunction "A_2") (pintype "passive"))
      (node (ref "SW_Eb7") (pin "2") (pinfunction "2_2") (pintype "passive"))
    )
    (net (code "28") (name "Net-(D16-A)") (class "Default")
      (node (ref "D16") (pin "2") (pinfunction "A_2") (pintype "passive"))
      (node (ref "SW_Bb7") (pin "2") (pinfunction "2_2") (pintype "passive"))
    )
    (net (code "29") (name "Net-(D17-A)") (class "Default")
      (node (ref "D17") (pin "2") (pinfunction "A_2") (pintype "passive"))
      (node (ref "SW_F7") (pin "2") (pinfunction "2_2") (pintype "passive"))
    )
    (net (code "30") (name "Net-(D18-A)") (class "Default")
      (node (ref "D18") (pin "2") (pinfunction "A_2") (pintype "passive"))
      (node (ref "SW_C7") (pin "2") (pinfunction "2_2") (pintype "passive"))
    )
    (net (code "31") (name "Net-(D19-A)") (class "Default")
      (node (ref "D19") (pin "2") (pinfunction "A_2") (pintype "passive"))
      (node (ref "SW_GMA") (pin "2") (pinfunction "2_2") (pintype "passive"))
    )
    (net (code "32") (name "Net-(D20-A)") (class "Default")
      (node (ref "D20") (pin "2") (pinfunction "A_2") (pintype "passive"))
      (node (ref "SW_DMA") (pin "2") (pinfunction "2_2") (pintype "passive"))
    )
    (net (code "33") (name "Net-(D21-A)") (class "Default")
      (node (ref "D21") (pin "2") (pinfunction "A_2") (pintype "passive"))
      (node (ref "SW_AMA") (pin "2") (pinfunction "2_2") (pintype "passive"))
    )
    (net (code "34") (name "Net-(D22-A)") (class "Default")
      (node (ref "D22") (pin "2") (pinfunction "A_2") (pintype "passive"))
      (node (ref "SW_EMA") (pin "2") (pinfunction "2_2") (pintype "passive"))
    )
    (net (code "35") (name "Net-(D23-A)") (class "Default")
      (node (ref "D23") (pin "2") (pinfunction "A_2") (pintype "passive"))
      (node (ref "SW_BMA") (pin "2") (pinfunction "2_2") (pintype "passive"))
    )
    (net (code "36") (name "Net-(D24-A)") (class "Default")
      (node (ref "D24") (pin "2") (pinfunction "A_2") (pintype "passive"))
      (node (ref "SW_FsMA") (pin "2") (pinfunction "2_2") (pintype "passive"))
    )
    (net (code "37") (name "Net-(D25-A)") (class "Default")
      (node (ref "D25") (pin "2") (pinfunction "A_2") (pintype "passive"))
      (node (ref "SW_Gmi") (pin "2") (pinfunction "2_2") (pintype "passive"))
    )
    (net (code "38") (name "Net-(D26-A)") (class "Default")
      (node (ref "D26") (pin "2") (pinfunction "A_2") (pintype "passive"))
      (node (ref "SW_Dmi") (pin "2") (pinfunction "2_2") (pintype "passive"))
    )
    (net (code "39") (name "Net-(D27-A)") (class "Default")
      (node (ref "D27") (pin "2") (pinfunction "A_2") (pintype "passive"))
      (node (ref "SW_Ami") (pin "2") (pinfunction "2_2") (pintype "passive"))
    )
    (net (code "40") (name "Net-(D28-A)") (class "Default")
      (node (ref "D28") (pin "2") (pinfunction "A_2") (pintype "passive"))
      (node (ref "SW_Emi") (pin "2") (pinfunction "2_2") (pintype "passive"))
    )
    (net (code "41") (name "Net-(D29-A)") (class "Default")
      (node (ref "D29") (pin "2") (pinfunction "A_2") (pintype "passive"))
      (node (ref "SW_Bmi") (pin "2") (pinfunction "2_2") (pintype "passive"))
    )
    (net (code "42") (name "Net-(D30-A)") (class "Default")
      (node (ref "D30") (pin "2") (pinfunction "A_2") (pintype "passive"))
      (node (ref "SW_Fsmi") (pin "2") (pinfunction "2_2") (pintype "passive"))
    )
    (net (code "43") (name "Net-(D31-A)") (class "Default")
      (node (ref "D31") (pin "2") (pinfunction "A_2") (pintype "passive"))
      (node (ref "SW_G7") (pin "2") (pinfunction "2_2") (pintype "passive"))
    )
    (net (code "44") (name "Net-(D32-A)") (class "Default")
      (node (ref "D32") (pin "2") (pinfunction "A_2") (pintype "passive"))
      (node (ref "SW_D7") (pin "2") (pinfunction "2_2") (pintype "passive"))
    )
    (net (code "45") (name "Net-(D33-A)") (class "Default")
      (node (ref "D33") (pin "2") (pinfunction "A_2") (pintype "passive"))
      (node (ref "SW_A7") (pin "2") (pinfunction "2_2") (pintype "passive"))
    )
    (net (code "46") (name "Net-(D34-A)") (class "Default")
      (node (ref "D34") (pin "2") (pinfunction "A_2") (pintype "passive"))
      (node (ref "SW_E7") (pin "2") (pinfunction "2_2") (pintype "passive"))
    )
    (net (code "47") (name "Net-(D35-A)") (class "Default")
      (node (ref "D35") (pin "2") (pinfunction "A_2") (pintype "passive"))
      (node (ref "SW_B7") (pin "2") (pinfunction "2_2") (pintype "passive"))
    )
    (net (code "48") (name "Net-(D36-A)") (class "Default")
      (node (ref "D36") (pin "2") (pinfunction "A_2") (pintype "passive"))
      (node (ref "SW_Fs7") (pin "2") (pinfunction "2_2") (pintype "passive"))
    )
  )
)
